# Underwater_ROV_ESCS.net
KiCad netlist of a schematic drawn in Altium Designer
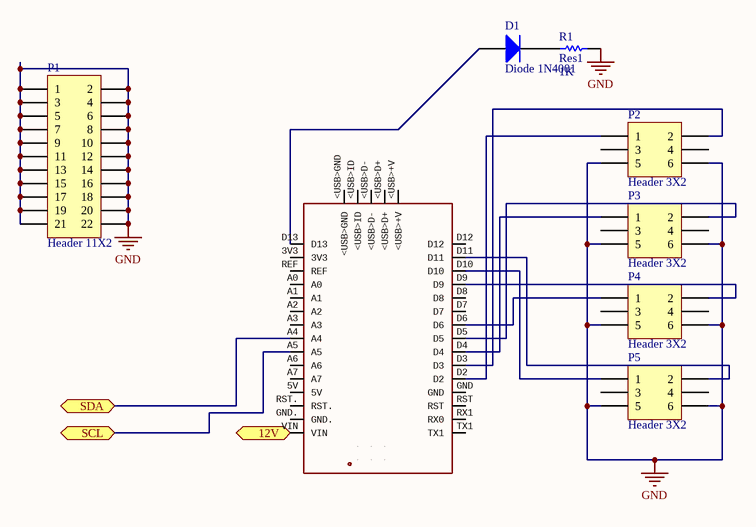
[diagram p0: Underwater_ROV_ESCS.SchDoc]

(export (version "E")
  (design (tool "Eeschema 10.0.6"))
  (components
    (comp (ref "D1")
      (value "Diode 1N4001")
      (footprint "DO-41")
      (description "1 Amp General Purpose Rectifier")
      (fields (field (name "PUBLISHER") "Altium Limited"))
      (libsource (lib "Miscellaneous Devices") (part "Diode 1N4001"))
    )
    (comp (ref "Nano_ESC")
      (value "Device for representing an Arduino Nano board with a footprint in an EAGLE design. Created by Dave Young for Element14. More EAGLE documentation at: http://www.element14.com/community/community/knode/cadsoft_eagle")
      (footprint "ARDUINO_NANO")
      (libsource (lib "E14_Arduino_revC") (part "ARDUINO_NANO"))
    )
    (comp (ref "P1")
      (value "Header 11X2")
      (footprint "HDR2X11")
      (description "Header, 11-Pin, Dual row")
      (fields (field (name "PUBLISHER") "Altium Limited"))
      (libsource (lib "Miscellaneous Connectors") (part "Header 11X2"))
    )
    (comp (ref "P2")
      (value "Header 3X2")
      (footprint "HDR2X3")
      (description "Header, 3-Pin, Dual row")
      (fields (field (name "PUBLISHER") "Altium Limited"))
      (libsource (lib "Miscellaneous Connectors") (part "Header 3X2"))
    )
    (comp (ref "P3")
      (value "Header 3X2")
      (footprint "HDR2X3")
      (description "Header, 3-Pin, Dual row")
      (fields (field (name "PUBLISHER") "Altium Limited"))
      (libsource (lib "Miscellaneous Connectors") (part "Header 3X2"))
    )
    (comp (ref "P4")
      (value "Header 3X2")
      (footprint "HDR2X3")
      (description "Header, 3-Pin, Dual row")
      (fields (field (name "PUBLISHER") "Altium Limited"))
      (libsource (lib "Miscellaneous Connectors") (part "Header 3X2"))
    )
    (comp (ref "P5")
      (value "Header 3X2")
      (footprint "HDR2X3")
      (description "Header, 3-Pin, Dual row")
      (fields (field (name "PUBLISHER") "Altium Limited"))
      (libsource (lib "Miscellaneous Connectors") (part "Header 3X2"))
    )
    (comp (ref "R1")
      (value "Res1")
      (footprint "AXIAL-0.3")
      (description "Resistor")
      (fields (field (name "ALTIUM_VALUE") "1K") (field (name "PUBLISHER") "Altium Limited"))
      (libsource (lib "Miscellaneous Devices") (part "Res1"))
    )
  )
  (nets
    (net (code "1") (name "/12V") (class "Default")
      (node (ref "Nano_ESC") (pin "VIN") (pinfunction "VIN_VIN") (pintype "passive"))
    )
    (net (code "2") (name "/SCL") (class "Default")
      (node (ref "Nano_ESC") (pin "A5") (pinfunction "A5_A5") (pintype "passive"))
    )
    (net (code "3") (name "/SDA") (class "Default")
      (node (ref "Nano_ESC") (pin "A4") (pinfunction "A4_A4") (pintype "passive"))
    )
    (net (code "4") (name "GND") (class "Default")
      (node (ref "P1") (pin "1") (pinfunction "1_1") (pintype "passive"))
      (node (ref "P1") (pin "10") (pinfunction "10_10") (pintype "passive"))
      (node (ref "P1") (pin "11") (pinfunction "11_11") (pintype "passive"))
      (node (ref "P1") (pin "12") (pinfunction "12_12") (pintype "passive"))
      (node (ref "P1") (pin "13") (pinfunction "13_13") (pintype "passive"))
      (node (ref "P1") (pin "14") (pinfunction "14_14") (pintype "passive"))
      (node (ref "P1") (pin "15") (pinfunction "15_15") (pintype "passive"))
      (node (ref "P1") (pin "16") (pinfunction "16_16") (pintype "passive"))
      (node (ref "P1") (pin "17") (pinfunction "17_17") (pintype "passive"))
      (node (ref "P1") (pin "18") (pinfunction "18_18") (pintype "passive"))
      (node (ref "P1") (pin "19") (pinfunction "19_19") (pintype "passive"))
      (node (ref "P1") (pin "2") (pinfunction "2_2") (pintype "passive"))
      (node (ref "P1") (pin "20") (pinfunction "20_20") (pintype "passive"))
      (node (ref "P1") (pin "21") (pinfunction "21_21") (pintype "passive"))
      (node (ref "P1") (pin "22") (pinfunction "22_22") (pintype "passive"))
      (node (ref "P1") (pin "3") (pinfunction "3_3") (pintype "passive"))
      (node (ref "P1") (pin "4") (pinfunction "4_4") (pintype "passive"))
      (node (ref "P1") (pin "5") (pinfunction "5_5") (pintype "passive"))
      (node (ref "P1") (pin "6") (pinfunction "6_6") (pintype "passive"))
      (node (ref "P1") (pin "7") (pinfunction "7_7") (pintype "passive"))
      (node (ref "P1") (pin "8") (pinfunction "8_8") (pintype "passive"))
      (node (ref "P1") (pin "9") (pinfunction "9_9") (pintype "passive"))
      (node (ref "P2") (pin "5") (pinfunction "5_5") (pintype "passive"))
      (node (ref "P2") (pin "6") (pinfunction "6_6") (pintype "passive"))
      (node (ref "P3") (pin "5") (pinfunction "5_5") (pintype "passive"))
      (node (ref "P3") (pin "6") (pinfunction "6_6") (pintype "passive"))
      (node (ref "P4") (pin "5") (pinfunction "5_5") (pintype "passive"))
      (node (ref "P4") (pin "6") (pinfunction "6_6") (pintype "passive"))
      (node (ref "P5") (pin "5") (pinfunction "5_5") (pintype "passive"))
      (node (ref "P5") (pin "6") (pinfunction "6_6") (pintype "passive"))
      (node (ref "R1") (pin "2") (pinfunction "2_2") (pintype "passive"))
    )
    (net (code "5") (name "Net-(D1-A)") (class "Default")
      (node (ref "D1") (pin "1") (pinfunction "A_1") (pintype "passive"))
      (node (ref "Nano_ESC") (pin "D13") (pinfunction "D13_D13") (pintype "passive"))
    )
    (net (code "6") (name "Net-(D1-K)") (class "Default")
      (node (ref "D1") (pin "2") (pinfunction "K_2") (pintype "passive"))
      (node (ref "R1") (pin "1") (pinfunction "1_1") (pintype "passive"))
    )
    (net (code "7") (name "Net-(Nano_ESC-PadD2)") (class "Default")
      (node (ref "Nano_ESC") (pin "D2") (pinfunction "D2_D2") (pintype "passive"))
      (node (ref "P2") (pin "1") (pinfunction "1_1") (pintype "passive"))
    )
    (net (code "8") (name "Net-(Nano_ESC-PadD3)") (class "Default")
      (node (ref "Nano_ESC") (pin "D3") (pinfunction "D3_D3") (pintype "passive"))
      (node (ref "P2") (pin "2") (pinfunction "2_2") (pintype "passive"))
    )
    (net (code "9") (name "Net-(Nano_ESC-PadD4)") (class "Default")
      (node (ref "Nano_ESC") (pin "D4") (pinfunction "D4_D4") (pintype "passive"))
      (node (ref "P3") (pin "1") (pinfunction "1_1") (pintype "passive"))
    )
    (net (code "10") (name "Net-(Nano_ESC-PadD5)") (class "Default")
      (node (ref "Nano_ESC") (pin "D5") (pinfunction "D5_D5") (pintype "passive"))
      (node (ref "P3") (pin "2") (pinfunction "2_2") (pintype "passive"))
    )
    (net (code "11") (name "Net-(Nano_ESC-PadD6)") (class "Default")
      (node (ref "Nano_ESC") (pin "D6") (pinfunction "D6_D6") (pintype "passive"))
      (node (ref "P4") (pin "1") (pinfunction "1_1") (pintype "passive"))
    )
    (net (code "12") (name "Net-(Nano_ESC-PadD9)") (class "Default")
      (node (ref "Nano_ESC") (pin "D9") (pinfunction "D9_D9") (pintype "passive"))
      (node (ref "P4") (pin "2") (pinfunction "2_2") (pintype "passive"))
    )
    (net (code "13") (name "Net-(Nano_ESC-PadD10)") (class "Default")
      (node (ref "Nano_ESC") (pin "D10") (pinfunction "D10_D10") (pintype "passive"))
      (node (ref "P5") (pin "1") (pinfunction "1_1") (pintype "passive"))
    )
    (net (code "14") (name "Net-(Nano_ESC-PadD11)") (class "Default")
      (node (ref "Nano_ESC") (pin "D11") (pinfunction "D11_D11") (pintype "passive"))
      (node (ref "P5") (pin "2") (pinfunction "2_2") (pintype "passive"))
    )
    (net (code "15") (name "unconnected-(Nano_ESC-Pad3V3)") (class "Default")
      (node (ref "Nano_ESC") (pin "3V3") (pinfunction "3V3_3V3") (pintype "passive"))
    )
    (net (code "16") (name "unconnected-(Nano_ESC-Pad5V)") (class "Default")
      (node (ref "Nano_ESC") (pin "5V") (pinfunction "5V_5V") (pintype "passive"))
    )
    (net (code "17") (name "unconnected-(Nano_ESC-Pad5V.)") (class "Default")
      (node (ref "Nano_ESC") (pin "5V.") (pinfunction "5V._5V.") (pintype "passive"))
    )
    (net (code "18") (name "unconnected-(Nano_ESC-Pad<USB>+V)") (class "Default")
      (node (ref "Nano_ESC") (pin "<USB>+V") (pinfunction "<USB>+V_<USB>+V") (pintype "passive"))
    )
    (net (code "19") (name "unconnected-(Nano_ESC-Pad<USB>D+)") (class "Default")
      (node (ref "Nano_ESC") (pin "<USB>D+") (pinfunction "<USB>D+_<USB>D+") (pintype "passive"))
    )
    (net (code "20") (name "unconnected-(Nano_ESC-Pad<USB>D-)") (class "Default")
      (node (ref "Nano_ESC") (pin "<USB>D-") (pinfunction "<USB>D-_<USB>D-") (pintype "passive"))
    )
    (net (code "21") (name "unconnected-(Nano_ESC-Pad<USB>GND)") (class "Default")
      (node (ref "Nano_ESC") (pin "<USB>GND") (pinfunction "<USB>GND_<USB>GND") (pintype "passive"))
    )
    (net (code "22") (name "unconnected-(Nano_ESC-Pad<USB>ID)") (class "Default")
      (node (ref "Nano_ESC") (pin "<USB>ID") (pinfunction "<USB>ID_<USB>ID") (pintype "passive"))
    )
    (net (code "23") (name "unconnected-(Nano_ESC-PadA0)") (class "Default")
      (node (ref "Nano_ESC") (pin "A0") (pinfunction "A0_A0") (pintype "passive"))
    )
    (net (code "24") (name "unconnected-(Nano_ESC-PadA1)") (class "Default")
      (node (ref "Nano_ESC") (pin "A1") (pinfunction "A1_A1") (pintype "passive"))
    )
    (net (code "25") (name "unconnected-(Nano_ESC-PadA2)") (class "Default")
      (node (ref "Nano_ESC") (pin "A2") (pinfunction "A2_A2") (pintype "passive"))
    )
    (net (code "26") (name "unconnected-(Nano_ESC-PadA3)") (class "Default")
      (node (ref "Nano_ESC") (pin "A3") (pinfunction "A3_A3") (pintype "passive"))
    )
    (net (code "27") (name "unconnected-(Nano_ESC-PadA6)") (class "Default")
      (node (ref "Nano_ESC") (pin "A6") (pinfunction "A6_A6") (pintype "passive"))
    )
    (net (code "28") (name "unconnected-(Nano_ESC-PadA7)") (class "Default")
      (node (ref "Nano_ESC") (pin "A7") (pinfunction "A7_A7") (pintype "passive"))
    )
    (net (code "29") (name "unconnected-(Nano_ESC-PadD7)") (class "Default")
      (node (ref "Nano_ESC") (pin "D7") (pinfunction "D7_D7") (pintype "passive"))
    )
    (net (code "30") (name "unconnected-(Nano_ESC-PadD8)") (class "Default")
      (node (ref "Nano_ESC") (pin "D8") (pinfunction "D8_D8") (pintype "passive"))
    )
    (net (code "31") (name "unconnected-(Nano_ESC-PadD12)") (class "Default")
      (node (ref "Nano_ESC") (pin "D12") (pinfunction "D12_D12") (pintype "passive"))
    )
    (net (code "32") (name "unconnected-(Nano_ESC-PadGND)") (class "Default")
      (node (ref "Nano_ESC") (pin "GND") (pinfunction "GND_GND") (pintype "passive"))
    )
    (net (code "33") (name "unconnected-(Nano_ESC-PadGND.)") (class "Default")
      (node (ref "Nano_ESC") (pin "GND.") (pinfunction "GND._GND.") (pintype "passive"))
    )
    (net (code "34") (name "unconnected-(Nano_ESC-PadGND_)") (class "Default")
      (node (ref "Nano_ESC") (pin "GND_") (pinfunction "GND__GND_") (pintype "passive"))
    )
    (net (code "35") (name "unconnected-(Nano_ESC-PadMISO)") (class "Default")
      (node (ref "Nano_ESC") (pin "MISO") (pinfunction "MISO_MISO") (pintype "passive"))
    )
    (net (code "36") (name "unconnected-(Nano_ESC-PadMOSI)") (class "Default")
      (node (ref "Nano_ESC") (pin "MOSI") (pinfunction "MOSI_MOSI") (pintype "passive"))
    )
    (net (code "37") (name "unconnected-(Nano_ESC-PadREF)") (class "Default")
      (node (ref "Nano_ESC") (pin "REF") (pinfunction "REF_REF") (pintype "passive"))
    )
    (net (code "38") (name "unconnected-(Nano_ESC-PadRESET..)") (class "Default")
      (node (ref "Nano_ESC") (pin "RESET..") (pinfunction "RESET.._RESET..") (pintype "passive"))
    )
    (net (code "39") (name "unconnected-(Nano_ESC-PadRST)") (class "Default")
      (node (ref "Nano_ESC") (pin "RST") (pinfunction "RST_RST") (pintype "passive"))
    )
    (net (code "40") (name "unconnected-(Nano_ESC-PadRST.)") (class "Default")
      (node (ref "Nano_ESC") (pin "RST.") (pinfunction "RST._RST.") (pintype "passive"))
    )
    (net (code "41") (name "unconnected-(Nano_ESC-PadSCK)") (class "Default")
      (node (ref "Nano_ESC") (pin "SCK") (pinfunction "SCK_SCK") (pintype "passive"))
    )
    (net (code "42") (name "unconnected-(Nano_ESC-PadTX1)") (class "Default")
      (node (ref "Nano_ESC") (pin "TX1") (pinfunction "TX1_TX1") (pintype "passive"))
    )
    (net (code "43") (name "unconnected-(Nano_ESC-RX0-PadRX1)") (class "Default")
      (node (ref "Nano_ESC") (pin "RX1") (pinfunction "RX0_RX1") (pintype "passive"))
    )
    (net (code "44") (name "unconnected-(P2-Pad3)") (class "Default")
      (node (ref "P2") (pin "3") (pinfunction "3_3") (pintype "passive"))
    )
    (net (code "45") (name "unconnected-(P2-Pad4)") (class "Default")
      (node (ref "P2") (pin "4") (pinfunction "4_4") (pintype "passive"))
    )
    (net (code "46") (name "unconnected-(P3-Pad3)") (class "Default")
      (node (ref "P3") (pin "3") (pinfunction "3_3") (pintype "passive"))
    )
    (net (code "47") (name "unconnected-(P3-Pad4)") (class "Default")
      (node (ref "P3") (pin "4") (pinfunction "4_4") (pintype "passive"))
    )
    (net (code "48") (name "unconnected-(P4-Pad3)") (class "Default")
      (node (ref "P4") (pin "3") (pinfunction "3_3") (pintype "passive"))
    )
    (net (code "49") (name "unconnected-(P4-Pad4)") (class "Default")
      (node (ref "P4") (pin "4") (pinfunction "4_4") (pintype "passive"))
    )
    (net (code "50") (name "unconnected-(P5-Pad3)") (class "Default")
      (node (ref "P5") (pin "3") (pinfunction "3_3") (pintype "passive"))
    )
    (net (code "51") (name "unconnected-(P5-Pad4)") (class "Default")
      (node (ref "P5") (pin "4") (pinfunction "4_4") (pintype "passive"))
    )
  )
)
